# tick-box-1591b-shield-mk-1_0.net
KiCad netlist of a schematic drawn in EAGLE
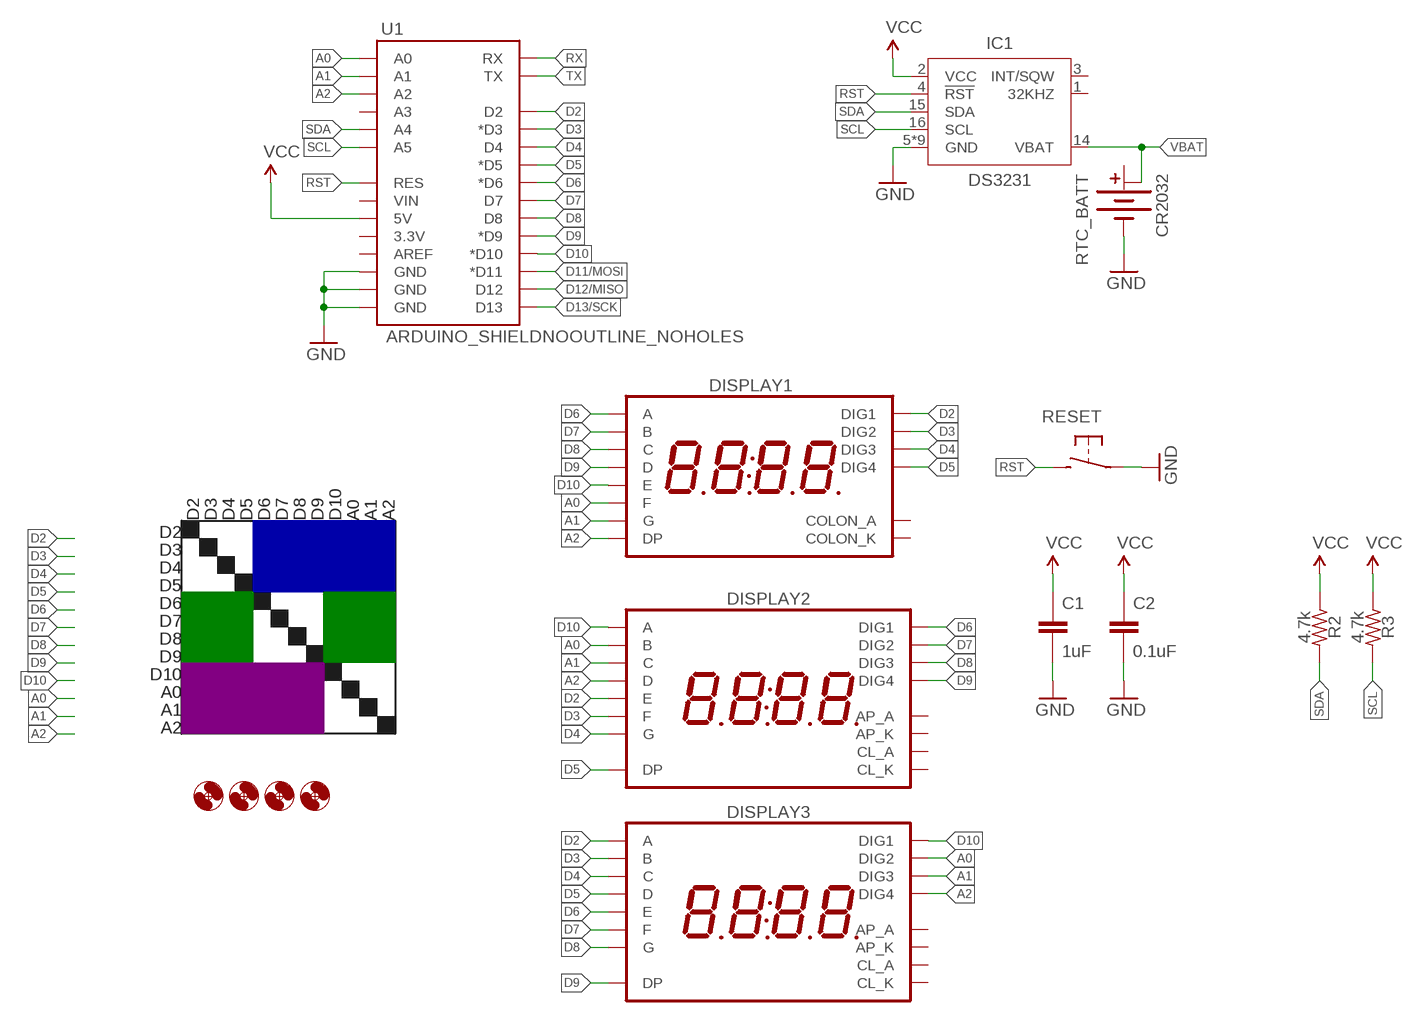
[diagram p0: schematic, sheet 1]

(export (version "E")
  (design (tool "Eeschema 10.0.6"))
  (components
    (comp (ref "C1")
      (value "1uF")
      (footprint "eagle-import:C025-024X044")
      (libsource (lib "eagle-import") (part "CAPACITOR-CERAMIC025-024X044"))
    )
    (comp (ref "C2")
      (value "0.1uF")
      (footprint "eagle-import:C025-024X044")
      (libsource (lib "eagle-import") (part "CAPACITOR-CERAMIC025-024X044"))
    )
    (comp (ref "DISPLAY1")
      (value "7SEG_4DIGIT_COLON14.2MM-CC-NS")
      (footprint "eagle-import:7SEG_4DIG_NS")
      (libsource (lib "eagle-import") (part "7SEG_4DIGIT_COLON14.2MM-CC-NS"))
    )
    (comp (ref "DISPLAY2")
      (value "7SEG_4DIGIT_COLON_APOS")
      (footprint "eagle-import:7SEG_4DIG_10MM")
      (libsource (lib "eagle-import") (part "7SEG_4DIGIT_COLON_APOS"))
    )
    (comp (ref "DISPLAY3")
      (value "7SEG_4DIGIT_COLON_APOS")
      (footprint "eagle-import:7SEG_4DIG_10MM")
      (libsource (lib "eagle-import") (part "7SEG_4DIGIT_COLON_APOS"))
    )
    (comp (ref "H1")
      (value "HOLE#2")
      (footprint "eagle-import:HOLE-#2")
      (libsource (lib "eagle-import") (part "HOLE#2"))
    )
    (comp (ref "H2")
      (value "HOLE#2")
      (footprint "eagle-import:HOLE-#2")
      (libsource (lib "eagle-import") (part "HOLE#2"))
    )
    (comp (ref "H3")
      (value "HOLE#2")
      (footprint "eagle-import:HOLE-#2")
      (libsource (lib "eagle-import") (part "HOLE#2"))
    )
    (comp (ref "H4")
      (value "HOLE#2")
      (footprint "eagle-import:HOLE-#2")
      (libsource (lib "eagle-import") (part "HOLE#2"))
    )
    (comp (ref "IC1")
      (value "DS3231")
      (footprint "eagle-import:SO16W")
      (libsource (lib "eagle-import") (part "DS3231"))
    )
    (comp (ref "R2")
      (value "4.7k")
      (footprint "eagle-import:RESISTOR-AXIAL-PTH-7.62MM")
      (libsource (lib "eagle-import") (part "RESISTORPTH-AXIAL-7.62MM"))
    )
    (comp (ref "R3")
      (value "4.7k")
      (footprint "eagle-import:RESISTOR-AXIAL-PTH-7.62MM")
      (libsource (lib "eagle-import") (part "RESISTORPTH-AXIAL-7.62MM"))
    )
    (comp (ref "RESET")
      (value "SPST-NO-TACT6MM-PTH-SMALL-PADS")
      (footprint "eagle-import:DTS-6-SMALL-PADS")
      (libsource (lib "eagle-import") (part "SPST-NO-TACT6MM-PTH-SMALL-PADS"))
    )
    (comp (ref "RTC_BATT")
      (value "CR2032")
      (footprint "eagle-import:BATTCON_20MM_MINE")
      (libsource (lib "eagle-import") (part "BATTERY-COINCR2032_SMD"))
    )
    (comp (ref "U1")
      (value "ARDUINO_SHIELDNOOUTLINE_NOHOLES")
      (footprint "eagle-import:ARDUINO_SHIELD_NOOUTLINE_NOHOLES")
      (libsource (lib "eagle-import") (part "ARDUINO_SHIELDNOOUTLINE_NOHOLES"))
    )
  )
  (nets
    (net (code "1") (name "A0") (class "Default")
      (node (ref "DISPLAY1") (pin "P$12") (pinfunction "F_P$12") (pintype "passive"))
      (node (ref "DISPLAY2") (pin "16") (pinfunction "B_16") (pintype "passive"))
      (node (ref "DISPLAY3") (pin "2") (pinfunction "DIG2_2") (pintype "passive"))
      (node (ref "U1") (pin "A0") (pinfunction "A0_A0") (pintype "bidirectional"))
    )
    (net (code "2") (name "A1") (class "Default")
      (node (ref "DISPLAY1") (pin "P$5") (pinfunction "G_P$5") (pintype "passive"))
      (node (ref "DISPLAY2") (pin "13") (pinfunction "C_13") (pintype "passive"))
      (node (ref "DISPLAY3") (pin "6") (pinfunction "DIG3_6") (pintype "passive"))
      (node (ref "U1") (pin "A1") (pinfunction "A1_A1") (pintype "bidirectional"))
    )
    (net (code "3") (name "A2") (class "Default")
      (node (ref "DISPLAY1") (pin "P$3") (pinfunction "DP_P$3") (pintype "passive"))
      (node (ref "DISPLAY2") (pin "3") (pinfunction "D_3") (pintype "passive"))
      (node (ref "DISPLAY3") (pin "8") (pinfunction "DIG4_8") (pintype "passive"))
      (node (ref "U1") (pin "A2") (pinfunction "A2_A2") (pintype "bidirectional"))
    )
    (net (code "4") (name "D2") (class "Default")
      (node (ref "DISPLAY1") (pin "P$14") (pinfunction "DIG1_P$14") (pintype "passive"))
      (node (ref "DISPLAY2") (pin "5") (pinfunction "E_5") (pintype "passive"))
      (node (ref "DISPLAY3") (pin "14") (pinfunction "A_14") (pintype "passive"))
      (node (ref "U1") (pin "D2") (pinfunction "D2_D2") (pintype "bidirectional"))
    )
    (net (code "5") (name "D3") (class "Default")
      (node (ref "DISPLAY1") (pin "P$11") (pinfunction "DIG2_P$11") (pintype "passive"))
      (node (ref "DISPLAY2") (pin "11") (pinfunction "F_11") (pintype "passive"))
      (node (ref "DISPLAY3") (pin "16") (pinfunction "B_16") (pintype "passive"))
      (node (ref "U1") (pin "D3") (pinfunction "*D3_D3") (pintype "bidirectional"))
    )
    (net (code "6") (name "D4") (class "Default")
      (node (ref "DISPLAY1") (pin "P$10") (pinfunction "DIG3_P$10") (pintype "passive"))
      (node (ref "DISPLAY2") (pin "15") (pinfunction "G_15") (pintype "passive"))
      (node (ref "DISPLAY3") (pin "13") (pinfunction "C_13") (pintype "passive"))
      (node (ref "U1") (pin "D4") (pinfunction "D4_D4") (pintype "bidirectional"))
    )
    (net (code "7") (name "D5") (class "Default")
      (node (ref "DISPLAY1") (pin "P$6") (pinfunction "DIG4_P$6") (pintype "passive"))
      (node (ref "DISPLAY2") (pin "7") (pinfunction "DP_7") (pintype "passive"))
      (node (ref "DISPLAY3") (pin "3") (pinfunction "D_3") (pintype "passive"))
      (node (ref "U1") (pin "D5") (pinfunction "*D5_D5") (pintype "bidirectional"))
    )
    (net (code "8") (name "D6") (class "Default")
      (node (ref "DISPLAY1") (pin "P$13") (pinfunction "A_P$13") (pintype "passive"))
      (node (ref "DISPLAY2") (pin "1") (pinfunction "DIG1_1") (pintype "passive"))
      (node (ref "DISPLAY3") (pin "5") (pinfunction "E_5") (pintype "passive"))
      (node (ref "U1") (pin "D6") (pinfunction "*D6_D6") (pintype "bidirectional"))
    )
    (net (code "9") (name "D7") (class "Default")
      (node (ref "DISPLAY1") (pin "P$9") (pinfunction "B_P$9") (pintype "passive"))
      (node (ref "DISPLAY2") (pin "2") (pinfunction "DIG2_2") (pintype "passive"))
      (node (ref "DISPLAY3") (pin "11") (pinfunction "F_11") (pintype "passive"))
      (node (ref "U1") (pin "D7") (pinfunction "D7_D7") (pintype "bidirectional"))
    )
    (net (code "10") (name "D8") (class "Default")
      (node (ref "DISPLAY1") (pin "P$4") (pinfunction "C_P$4") (pintype "passive"))
      (node (ref "DISPLAY2") (pin "6") (pinfunction "DIG3_6") (pintype "passive"))
      (node (ref "DISPLAY3") (pin "15") (pinfunction "G_15") (pintype "passive"))
      (node (ref "U1") (pin "D8") (pinfunction "D8_D8") (pintype "bidirectional"))
    )
    (net (code "11") (name "D9") (class "Default")
      (node (ref "DISPLAY1") (pin "P$2") (pinfunction "D_P$2") (pintype "passive"))
      (node (ref "DISPLAY2") (pin "8") (pinfunction "DIG4_8") (pintype "passive"))
      (node (ref "DISPLAY3") (pin "7") (pinfunction "DP_7") (pintype "passive"))
      (node (ref "U1") (pin "D9") (pinfunction "*D9_D9") (pintype "bidirectional"))
    )
    (net (code "12") (name "D10") (class "Default")
      (node (ref "DISPLAY1") (pin "P$1") (pinfunction "E_P$1") (pintype "passive"))
      (node (ref "DISPLAY2") (pin "14") (pinfunction "A_14") (pintype "passive"))
      (node (ref "DISPLAY3") (pin "1") (pinfunction "DIG1_1") (pintype "passive"))
      (node (ref "U1") (pin "D10") (pinfunction "*D10_D10") (pintype "bidirectional"))
    )
    (net (code "13") (name "D11{slash}MOSI") (class "Default")
      (node (ref "U1") (pin "D11") (pinfunction "*D11_D11") (pintype "bidirectional"))
    )
    (net (code "14") (name "D12{slash}MISO") (class "Default")
      (node (ref "U1") (pin "D12") (pinfunction "D12_D12") (pintype "bidirectional"))
    )
    (net (code "15") (name "D13{slash}SCK") (class "Default")
      (node (ref "U1") (pin "D13") (pinfunction "D13_D13") (pintype "bidirectional"))
    )
    (net (code "16") (name "GND") (class "Default")
      (node (ref "C1") (pin "2") (pinfunction "2_2") (pintype "passive"))
      (node (ref "C2") (pin "2") (pinfunction "2_2") (pintype "passive"))
      (node (ref "IC1") (pin "10") (pinfunction "GND_10") (pintype "bidirectional"))
      (node (ref "IC1") (pin "11") (pinfunction "GND_11") (pintype "bidirectional"))
      (node (ref "IC1") (pin "12") (pinfunction "GND_12") (pintype "bidirectional"))
      (node (ref "IC1") (pin "13") (pinfunction "GND_13") (pintype "bidirectional"))
      (node (ref "IC1") (pin "5") (pinfunction "GND_5") (pintype "bidirectional"))
      (node (ref "IC1") (pin "6") (pinfunction "GND_6") (pintype "bidirectional"))
      (node (ref "IC1") (pin "7") (pinfunction "GND_7") (pintype "bidirectional"))
      (node (ref "IC1") (pin "8") (pinfunction "GND_8") (pintype "bidirectional"))
      (node (ref "IC1") (pin "9") (pinfunction "GND_9") (pintype "bidirectional"))
      (node (ref "RESET") (pin "1") (pinfunction "1_1") (pintype "passive"))
      (node (ref "RESET") (pin "2") (pinfunction "1_2") (pintype "passive"))
      (node (ref "RTC_BATT") (pin "BOTTOM") (pinfunction "-_BOTTOM") (pintype "bidirectional"))
      (node (ref "U1") (pin "GND@0") (pinfunction "GND_GND@0") (pintype "bidirectional"))
      (node (ref "U1") (pin "GND@1") (pinfunction "GND_GND@1") (pintype "bidirectional"))
      (node (ref "U1") (pin "GND@2") (pinfunction "GND_GND@2") (pintype "bidirectional"))
    )
    (net (code "17") (name "RST") (class "Default")
      (node (ref "IC1") (pin "4") (pinfunction "~{RST}_4") (pintype "bidirectional"))
      (node (ref "RESET") (pin "3") (pinfunction "2_3") (pintype "passive"))
      (node (ref "RESET") (pin "4") (pinfunction "2_4") (pintype "passive"))
      (node (ref "U1") (pin "RES") (pinfunction "RES_RES") (pintype "bidirectional"))
    )
    (net (code "18") (name "RX") (class "Default")
      (node (ref "U1") (pin "RX") (pinfunction "RX_RX") (pintype "bidirectional"))
    )
    (net (code "19") (name "SCL") (class "Default")
      (node (ref "IC1") (pin "16") (pinfunction "SCL_16") (pintype "bidirectional"))
      (node (ref "R3") (pin "P$2") (pinfunction "2_P$2") (pintype "passive"))
      (node (ref "U1") (pin "A5") (pinfunction "A5_A5") (pintype "bidirectional"))
    )
    (net (code "20") (name "SDA") (class "Default")
      (node (ref "IC1") (pin "15") (pinfunction "SDA_15") (pintype "bidirectional"))
      (node (ref "R2") (pin "P$2") (pinfunction "2_P$2") (pintype "passive"))
      (node (ref "U1") (pin "A4") (pinfunction "A4_A4") (pintype "bidirectional"))
    )
    (net (code "21") (name "TX") (class "Default")
      (node (ref "U1") (pin "TX") (pinfunction "TX_TX") (pintype "bidirectional"))
    )
    (net (code "22") (name "VBAT") (class "Default")
      (node (ref "IC1") (pin "14") (pinfunction "VBAT_14") (pintype "bidirectional"))
      (node (ref "RTC_BATT") (pin "TOP@2") (pinfunction "+1_TOP@2") (pintype "bidirectional"))
    )
    (net (code "23") (name "VCC") (class "Default")
      (node (ref "C1") (pin "1") (pinfunction "1_1") (pintype "passive"))
      (node (ref "C2") (pin "1") (pinfunction "1_1") (pintype "passive"))
      (node (ref "IC1") (pin "2") (pinfunction "VCC_2") (pintype "bidirectional"))
      (node (ref "R2") (pin "P$1") (pinfunction "1_P$1") (pintype "passive"))
      (node (ref "R3") (pin "P$1") (pinfunction "1_P$1") (pintype "passive"))
      (node (ref "U1") (pin "5V") (pinfunction "5V_5V") (pintype "bidirectional"))
    )
    (net (code "24") (name "unconnected-(DISPLAY1-COLON_A-PadP$8)") (class "Default")
      (node (ref "DISPLAY1") (pin "P$8") (pinfunction "COLON_A_P$8") (pintype "passive"))
    )
    (net (code "25") (name "unconnected-(DISPLAY1-COLON_K-PadP$7)") (class "Default")
      (node (ref "DISPLAY1") (pin "P$7") (pinfunction "COLON_K_P$7") (pintype "passive"))
    )
    (net (code "26") (name "unconnected-(DISPLAY2-AP_A-Pad10)") (class "Default")
      (node (ref "DISPLAY2") (pin "10") (pinfunction "AP_A_10") (pintype "bidirectional"))
    )
    (net (code "27") (name "unconnected-(DISPLAY2-AP_K-Pad9)") (class "Default")
      (node (ref "DISPLAY2") (pin "9") (pinfunction "AP_K_9") (pintype "bidirectional"))
    )
    (net (code "28") (name "unconnected-(DISPLAY2-CL_A-Pad4)") (class "Default")
      (node (ref "DISPLAY2") (pin "4") (pinfunction "CL_A_4") (pintype "passive"))
    )
    (net (code "29") (name "unconnected-(DISPLAY2-CL_K-Pad12)") (class "Default")
      (node (ref "DISPLAY2") (pin "12") (pinfunction "CL_K_12") (pintype "passive"))
    )
    (net (code "30") (name "unconnected-(DISPLAY3-AP_A-Pad10)") (class "Default")
      (node (ref "DISPLAY3") (pin "10") (pinfunction "AP_A_10") (pintype "bidirectional"))
    )
    (net (code "31") (name "unconnected-(DISPLAY3-AP_K-Pad9)") (class "Default")
      (node (ref "DISPLAY3") (pin "9") (pinfunction "AP_K_9") (pintype "bidirectional"))
    )
    (net (code "32") (name "unconnected-(DISPLAY3-CL_A-Pad4)") (class "Default")
      (node (ref "DISPLAY3") (pin "4") (pinfunction "CL_A_4") (pintype "passive"))
    )
    (net (code "33") (name "unconnected-(DISPLAY3-CL_K-Pad12)") (class "Default")
      (node (ref "DISPLAY3") (pin "12") (pinfunction "CL_K_12") (pintype "passive"))
    )
    (net (code "34") (name "unconnected-(IC1-32KHZ-Pad1)") (class "Default")
      (node (ref "IC1") (pin "1") (pinfunction "32KHZ_1") (pintype "bidirectional"))
    )
    (net (code "35") (name "unconnected-(IC1-INT{slash}SQW-Pad3)") (class "Default")
      (node (ref "IC1") (pin "3") (pinfunction "INT/SQW_3") (pintype "bidirectional"))
    )
    (net (code "36") (name "unconnected-(RTC_BATT-+-PadTOP@1)") (class "Default")
      (node (ref "RTC_BATT") (pin "TOP@1") (pinfunction "+_TOP@1") (pintype "bidirectional"))
    )
    (net (code "37") (name "unconnected-(U1-Pad3.3V)") (class "Default")
      (node (ref "U1") (pin "3.3V") (pinfunction "3.3V_3.3V") (pintype "bidirectional"))
    )
    (net (code "38") (name "unconnected-(U1-PadA3)") (class "Default")
      (node (ref "U1") (pin "A3") (pinfunction "A3_A3") (pintype "bidirectional"))
    )
    (net (code "39") (name "unconnected-(U1-PadAREF)") (class "Default")
      (node (ref "U1") (pin "AREF") (pinfunction "AREF_AREF") (pintype "bidirectional"))
    )
    (net (code "40") (name "unconnected-(U1-PadVIN)") (class "Default")
      (node (ref "U1") (pin "VIN") (pinfunction "VIN_VIN") (pintype "bidirectional"))
    )
  )
)
